# ATmega324PB_Xplained_Pro_dual_input_powe.net
KiCad netlist of a schematic drawn in Altium Designer
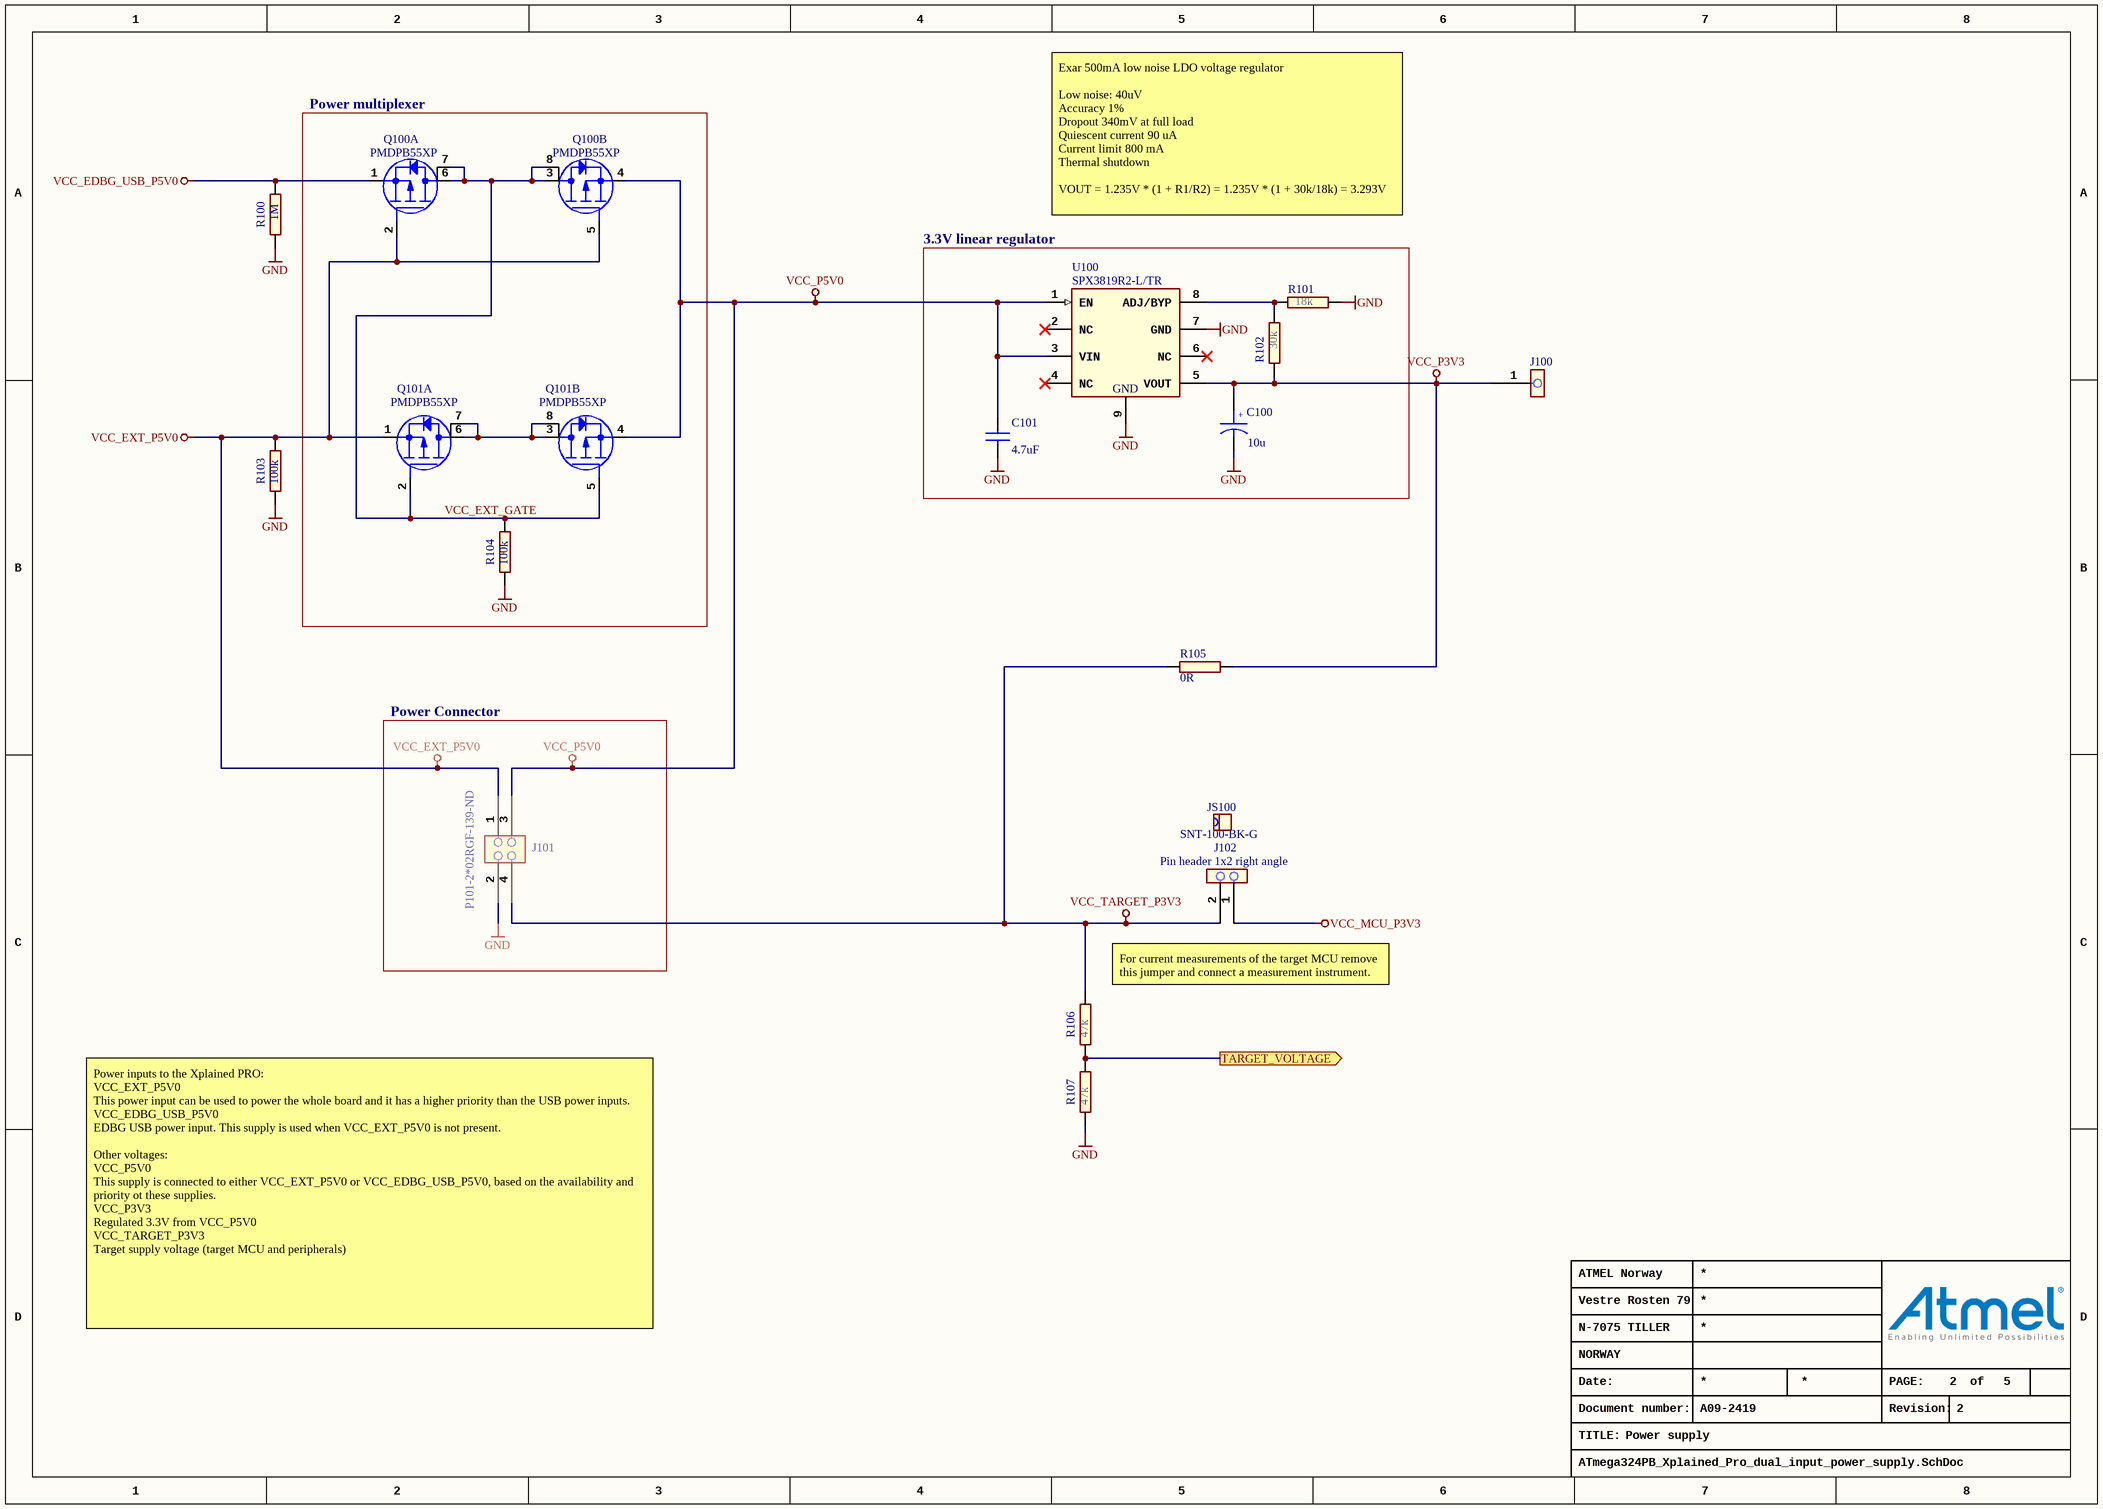
[diagram p0: ATmega324PB_Xplained_Pro_dual_input_power_supply.SchDoc]

(export (version "E")
  (design (tool "Eeschema 10.0.6"))
  (components
    (comp (ref "C100")
      (value "10u")
      (footprint "AP1-00036")
      (description "SMD tantalum capacitor, ESR = 1.7, 3216-18 (EIA) 1206,")
      (fields (field (name "TOLERANCE") "+-10%") (field (name "MANUFACTURER") "vishay"))
      (libsource (lib "AltiumDbLib") (part "CAP-POL"))
    )
    (comp (ref "C101")
      (value "4.7uF")
      (footprint "AP1-00039")
      (description "Ceramic capacitor, SMD 0603, X5R, 10V, 10% (de31036)")
      (fields (field (name "TOLERANCE") "10%") (field (name "MANUFACTURER") "tdk"))
      (libsource (lib "AltiumDbLib") (part "CAP-NONPOL"))
    )
    (comp (ref "J100")
      (value "~")
      (footprint "AP8-00976")
      (description "1x1 pin header, 2.54mm pitch, Pin-in-Paste THM")
      (fields (field (name "MANUFACTURER") "SAMTEC") (field (name "MPN") "HMTSW-101-23-F-S-237"))
      (libsource (lib "AltiumDbLib") (part "HEADER 1x1"))
    )
    (comp (ref "J101")
      (value "P101-2*02RGF-139-ND")
      (footprint "AP8-00628")
      (description "Pin header, 2x2, Right Angle, 2.54mm, THT, Pin In Paste")
      (fields (field (name "MANUFACTURER") "Pro-data International Corp"))
      (libsource (lib "AltiumDbLib") (part "HEADER 2x2"))
    )
    (comp (ref "J102")
      (value "Pin header 1x2 right angle")
      (footprint "AP8-00367")
      (description "1x2 pin header, right angle, 2.54 mm pitch, through-hole")
      (fields (field (name "MANUFACTURER") "Pro-data International Corp") (field (name "MPN") "2213R-2G"))
      (libsource (lib "AltiumDbLib") (part "HEADER 1x2"))
    )
    (comp (ref "JS100")
      (value "SNT-100-BK-G")
      (footprint "AP8-00525")
      (description "Jumper cap for 2.54mm pinheader")
      (fields (field (name "MANUFACTURER") "SAMTEC"))
      (libsource (lib "AltiumDbLib") (part "JUMPER_CAP"))
    )
    (comp (ref "Q100")
      (value "PMDPB55XP")
      (footprint "AP5-00047")
      (description "Dual P-Channel MOSFET, -20V, RDS(ON) < 55 mOhm @-3.4A@-4.5V")
      (fields (field (name "MANUFACTURER") "NXP") (field (name "Comment") "Farnell order code: 2191806"))
      (libsource (lib "AltiumDbLib") (part "MOSFET_DUAL_P_S1G1D2S2G2D1D1D2"))
    )
    (comp (ref "Q101")
      (value "PMDPB55XP")
      (footprint "AP5-00047")
      (description "Dual P-Channel MOSFET, -20V, RDS(ON) < 55 mOhm @-3.4A@-4.5V")
      (fields (field (name "MANUFACTURER") "NXP") (field (name "Comment") "Farnell order code: 2191806"))
      (libsource (lib "AltiumDbLib") (part "MOSFET_DUAL_P_S1G1D2S2G2D1D1D2"))
    )
    (comp (ref "R100")
      (value "1M")
      (footprint "AP2-00000")
      (description "Thick film resistor, SMD 0402, 1/16W, 1%")
      (fields (field (name "TOLERANCE") "1 %"))
      (libsource (lib "AltiumDbLib") (part "R2"))
    )
    (comp (ref "R101")
      (value "18k")
      (footprint "AP2-00000")
      (description "Thick film resistor, SMD 0402, 1/16W, 1%")
      (fields (field (name "TOLERANCE") "1 %"))
      (libsource (lib "") (part "R2_2"))
    )
    (comp (ref "R102")
      (value "30k")
      (footprint "AP2-00000")
      (description "Thick film resistor, SMD 0402, 1/16W, 1%")
      (fields (field (name "TOLERANCE") "1 %"))
      (libsource (lib "AltiumDbLib") (part "R2"))
    )
    (comp (ref "R103")
      (value "100k")
      (footprint "AP2-00000")
      (description "Thick film resistor, SMD 0402, 1/16W, 1%")
      (fields (field (name "TOLERANCE") "1 %"))
      (libsource (lib "AltiumDbLib") (part "R2"))
    )
    (comp (ref "R104")
      (value "100k")
      (footprint "AP2-00000")
      (description "Thick film resistor, SMD 0402, 1/16W, 1%")
      (fields (field (name "TOLERANCE") "1 %"))
      (libsource (lib "AltiumDbLib") (part "R2"))
    )
    (comp (ref "R105")
      (value "0R")
      (footprint "AP2-00000")
      (description "RES 0.0 OHM 1/16W 0402 SMD")
      (fields (field (name "TOLERANCE") "1 %") (field (name "MANUFACTURER") "(n/a)"))
      (libsource (lib "") (part "R2_2"))
    )
    (comp (ref "R106")
      (value "47k")
      (footprint "AP2-00000")
      (description "Thick film resistor, SMD 0402, 1/16W, 1%")
      (fields (field (name "TOLERANCE") "1 %"))
      (libsource (lib "") (part "R2_1"))
    )
    (comp (ref "R107")
      (value "47k")
      (footprint "AP2-00000")
      (description "Thick film resistor, SMD 0402, 1/16W, 1%")
      (fields (field (name "TOLERANCE") "1 %"))
      (libsource (lib "") (part "R2_1"))
    )
    (comp (ref "U100")
      (value "SPX3819R2-L/TR")
      (footprint "AP6-00338")
      (description "500mA LDO, ADJ, low noise, 8-DFN package")
      (fields (field (name "TOLERANCE") "±1%") (field (name "MANUFACTURER") "Exar"))
      (libsource (lib "AltiumDbLib") (part "SPX3819R2-L"))
    )
  )
  (nets
    (net (code "1") (name "/TARGET_VOLTAGE") (class "Default")
      (node (ref "R106") (pin "1") (pinfunction "1_1") (pintype "passive"))
      (node (ref "R107") (pin "2") (pinfunction "2_2") (pintype "passive"))
    )
    (net (code "2") (name "/VCC_EXT_GATE") (class "Default")
      (node (ref "Q100") (pin "3") (pinfunction "D2_3") (pintype "passive"))
      (node (ref "Q100") (pin "6") (pinfunction "D1_6") (pintype "passive"))
      (node (ref "Q100") (pin "7") (pinfunction "D1_PAD_7") (pintype "passive"))
      (node (ref "Q100") (pin "8") (pinfunction "D2_PAD_8") (pintype "passive"))
      (node (ref "Q101") (pin "2") (pinfunction "G1_2") (pintype "passive"))
      (node (ref "Q101") (pin "5") (pinfunction "G2_5") (pintype "passive"))
      (node (ref "R104") (pin "2") (pinfunction "2_2") (pintype "passive"))
    )
    (net (code "3") (name "GND") (class "Default")
      (node (ref "C100") (pin "2") (pinfunction "2_2") (pintype "passive"))
      (node (ref "C101") (pin "2") (pinfunction "2_2") (pintype "passive"))
      (node (ref "J101") (pin "2") (pinfunction "2_2") (pintype "passive"))
      (node (ref "R100") (pin "1") (pinfunction "1_1") (pintype "passive"))
      (node (ref "R101") (pin "2") (pinfunction "2_2") (pintype "passive"))
      (node (ref "R103") (pin "1") (pinfunction "1_1") (pintype "passive"))
      (node (ref "R104") (pin "1") (pinfunction "1_1") (pintype "passive"))
      (node (ref "R107") (pin "1") (pinfunction "1_1") (pintype "passive"))
      (node (ref "U100") (pin "7") (pinfunction "GND_7") (pintype "power_in"))
      (node (ref "U100") (pin "9") (pinfunction "GND_9") (pintype "power_in"))
    )
    (net (code "4") (name "Net-(Q101A-D1)") (class "Default")
      (node (ref "Q101") (pin "3") (pinfunction "D2_3") (pintype "passive"))
      (node (ref "Q101") (pin "6") (pinfunction "D1_6") (pintype "passive"))
      (node (ref "Q101") (pin "7") (pinfunction "D1_PAD_7") (pintype "passive"))
      (node (ref "Q101") (pin "8") (pinfunction "D2_PAD_8") (pintype "passive"))
    )
    (net (code "5") (name "Net-(U100-ADJ{slash}BYP)") (class "Default")
      (node (ref "R101") (pin "1") (pinfunction "1_1") (pintype "passive"))
      (node (ref "R102") (pin "2") (pinfunction "2_2") (pintype "passive"))
      (node (ref "U100") (pin "8") (pinfunction "ADJ/BYP_8") (pintype "passive"))
    )
    (net (code "6") (name "VCC_EDBG_USB_P5V0") (class "Default")
      (node (ref "Q100") (pin "1") (pinfunction "S1_1") (pintype "passive"))
      (node (ref "R100") (pin "2") (pinfunction "2_2") (pintype "passive"))
    )
    (net (code "7") (name "VCC_EXT_P5V0") (class "Default")
      (node (ref "J101") (pin "1") (pinfunction "1_1") (pintype "passive"))
      (node (ref "Q100") (pin "2") (pinfunction "G1_2") (pintype "passive"))
      (node (ref "Q100") (pin "5") (pinfunction "G2_5") (pintype "passive"))
      (node (ref "Q101") (pin "1") (pinfunction "S1_1") (pintype "passive"))
      (node (ref "R103") (pin "2") (pinfunction "2_2") (pintype "passive"))
    )
    (net (code "8") (name "VCC_MCU_P3V3") (class "Default")
      (node (ref "J102") (pin "1") (pinfunction "1_1") (pintype "passive"))
    )
    (net (code "9") (name "VCC_P3V3") (class "Default")
      (node (ref "C100") (pin "1") (pinfunction "1_1") (pintype "passive"))
      (node (ref "J100") (pin "1") (pinfunction "1_1") (pintype "passive"))
      (node (ref "R102") (pin "1") (pinfunction "1_1") (pintype "passive"))
      (node (ref "R105") (pin "2") (pinfunction "2_2") (pintype "passive"))
      (node (ref "U100") (pin "5") (pinfunction "VOUT_5") (pintype "power_in"))
    )
    (net (code "10") (name "VCC_P5V0") (class "Default")
      (node (ref "C101") (pin "1") (pinfunction "1_1") (pintype "passive"))
      (node (ref "J101") (pin "3") (pinfunction "3_3") (pintype "passive"))
      (node (ref "Q100") (pin "4") (pinfunction "S2_4") (pintype "passive"))
      (node (ref "Q101") (pin "4") (pinfunction "S2_4") (pintype "passive"))
      (node (ref "U100") (pin "1") (pinfunction "EN_1") (pintype "input"))
      (node (ref "U100") (pin "3") (pinfunction "VIN_3") (pintype "power_in"))
    )
    (net (code "11") (name "VCC_TARGET_P3V3") (class "Default")
      (node (ref "J101") (pin "4") (pinfunction "4_4") (pintype "passive"))
      (node (ref "J102") (pin "2") (pinfunction "2_2") (pintype "passive"))
      (node (ref "R105") (pin "1") (pinfunction "1_1") (pintype "passive"))
      (node (ref "R106") (pin "2") (pinfunction "2_2") (pintype "passive"))
    )
    (net (code "12") (name "unconnected-(U100-NC-Pad2)") (class "Default")
      (node (ref "U100") (pin "2") (pinfunction "NC_2") (pintype "passive+no_connect"))
    )
    (net (code "13") (name "unconnected-(U100-NC-Pad4)") (class "Default")
      (node (ref "U100") (pin "4") (pinfunction "NC_4") (pintype "passive+no_connect"))
    )
    (net (code "14") (name "unconnected-(U100-NC-Pad6)") (class "Default")
      (node (ref "U100") (pin "6") (pinfunction "NC_6") (pintype "passive+no_connect"))
    )
  )
)
